# Sheet1.net
KiCad netlist of a schematic drawn in Altium Designer
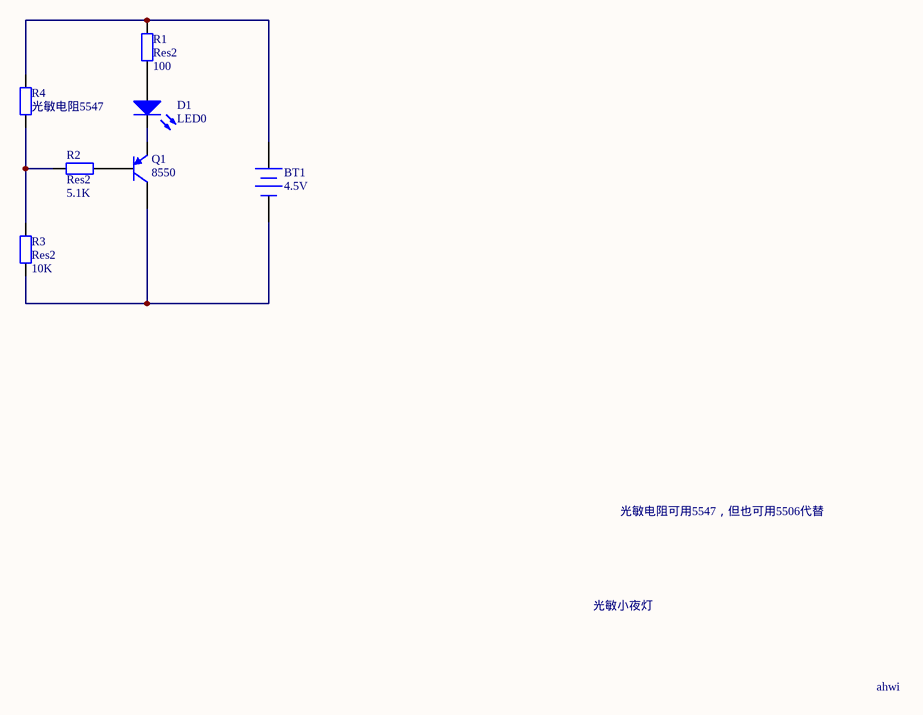
[diagram p0: Sheet1.SchDoc]

(export (version "E")
  (design (tool "Eeschema 10.0.6"))
  (components
    (comp (ref "BT1")
      (value "4.5V")
      (footprint "BAT-2")
      (description "Multicell Battery")
      (fields (field (name "PUBLISHER") "Altium Limited"))
      (libsource (lib "Miscellaneous Devices") (part "Battery"))
    )
    (comp (ref "D1")
      (value "LED0")
      (footprint "6-0805_M")
      (description "Typical INFRARED GaAs LED")
      (fields (field (name "PUBLISHER") "Altium Limited"))
      (libsource (lib "Miscellaneous Devices") (part "LED0"))
    )
    (comp (ref "Q1")
      (value "8550")
      (footprint "SOT-23B_L")
      (description "PNP Bipolar Transistor")
      (fields (field (name "PUBLISHER") "Altium Limited"))
      (libsource (lib "Miscellaneous Devices") (part "PNP"))
    )
    (comp (ref "R1")
      (value "Res2")
      (footprint "6-0805_M")
      (description "Resistor")
      (fields (field (name "ALTIUM_VALUE") "100") (field (name "PUBLISHER") "Altium Limited"))
      (libsource (lib "") (part "Res2_1"))
    )
    (comp (ref "R2")
      (value "Res2")
      (footprint "6-0805_M")
      (description "Resistor")
      (fields (field (name "ALTIUM_VALUE") "5.1K") (field (name "PUBLISHER") "Altium Limited"))
      (libsource (lib "Miscellaneous Devices") (part "Res2"))
    )
    (comp (ref "R3")
      (value "Res2")
      (footprint "6-0805_M")
      (description "Resistor")
      (fields (field (name "ALTIUM_VALUE") "10K") (field (name "PUBLISHER") "Altium Limited"))
      (libsource (lib "") (part "Res2_1"))
    )
    (comp (ref "R4")
      (value "光敏电阻5547")
      (footprint "R38")
      (description "Resistor")
      (fields (field (name "PUBLISHER") "Altium Limited"))
      (libsource (lib "") (part "Res2_1"))
    )
  )
  (nets
    (net (code "1") (name "Net-(BT1-+)") (class "Default")
      (node (ref "BT1") (pin "1") (pinfunction "+_1") (pintype "passive"))
      (node (ref "R1") (pin "2") (pinfunction "2_2") (pintype "passive"))
      (node (ref "R4") (pin "2") (pinfunction "2_2") (pintype "passive"))
    )
    (net (code "2") (name "Net-(BT1--)") (class "Default")
      (node (ref "BT1") (pin "2") (pinfunction "-_2") (pintype "passive"))
      (node (ref "Q1") (pin "1") (pinfunction "C_1") (pintype "passive"))
      (node (ref "R3") (pin "1") (pinfunction "1_1") (pintype "passive"))
    )
    (net (code "3") (name "Net-(D1-A)") (class "Default")
      (node (ref "D1") (pin "1") (pinfunction "A_1") (pintype "passive"))
      (node (ref "R1") (pin "1") (pinfunction "1_1") (pintype "passive"))
    )
    (net (code "4") (name "Net-(D1-K)") (class "Default")
      (node (ref "D1") (pin "2") (pinfunction "K_2") (pintype "passive"))
      (node (ref "Q1") (pin "3") (pinfunction "E_3") (pintype "passive"))
    )
    (net (code "5") (name "Net-(Q1-B)") (class "Default")
      (node (ref "Q1") (pin "2") (pinfunction "B_2") (pintype "passive"))
      (node (ref "R2") (pin "2") (pinfunction "2_2") (pintype "passive"))
    )
    (net (code "6") (name "Net-(R2-Pad1)") (class "Default")
      (node (ref "R2") (pin "1") (pinfunction "1_1") (pintype "passive"))
      (node (ref "R3") (pin "2") (pinfunction "2_2") (pintype "passive"))
      (node (ref "R4") (pin "1") (pinfunction "1_1") (pintype "passive"))
    )
  )
)
